# PCM2706_CODEC_MAIN.net
KiCad netlist of a schematic drawn in Altium Designer
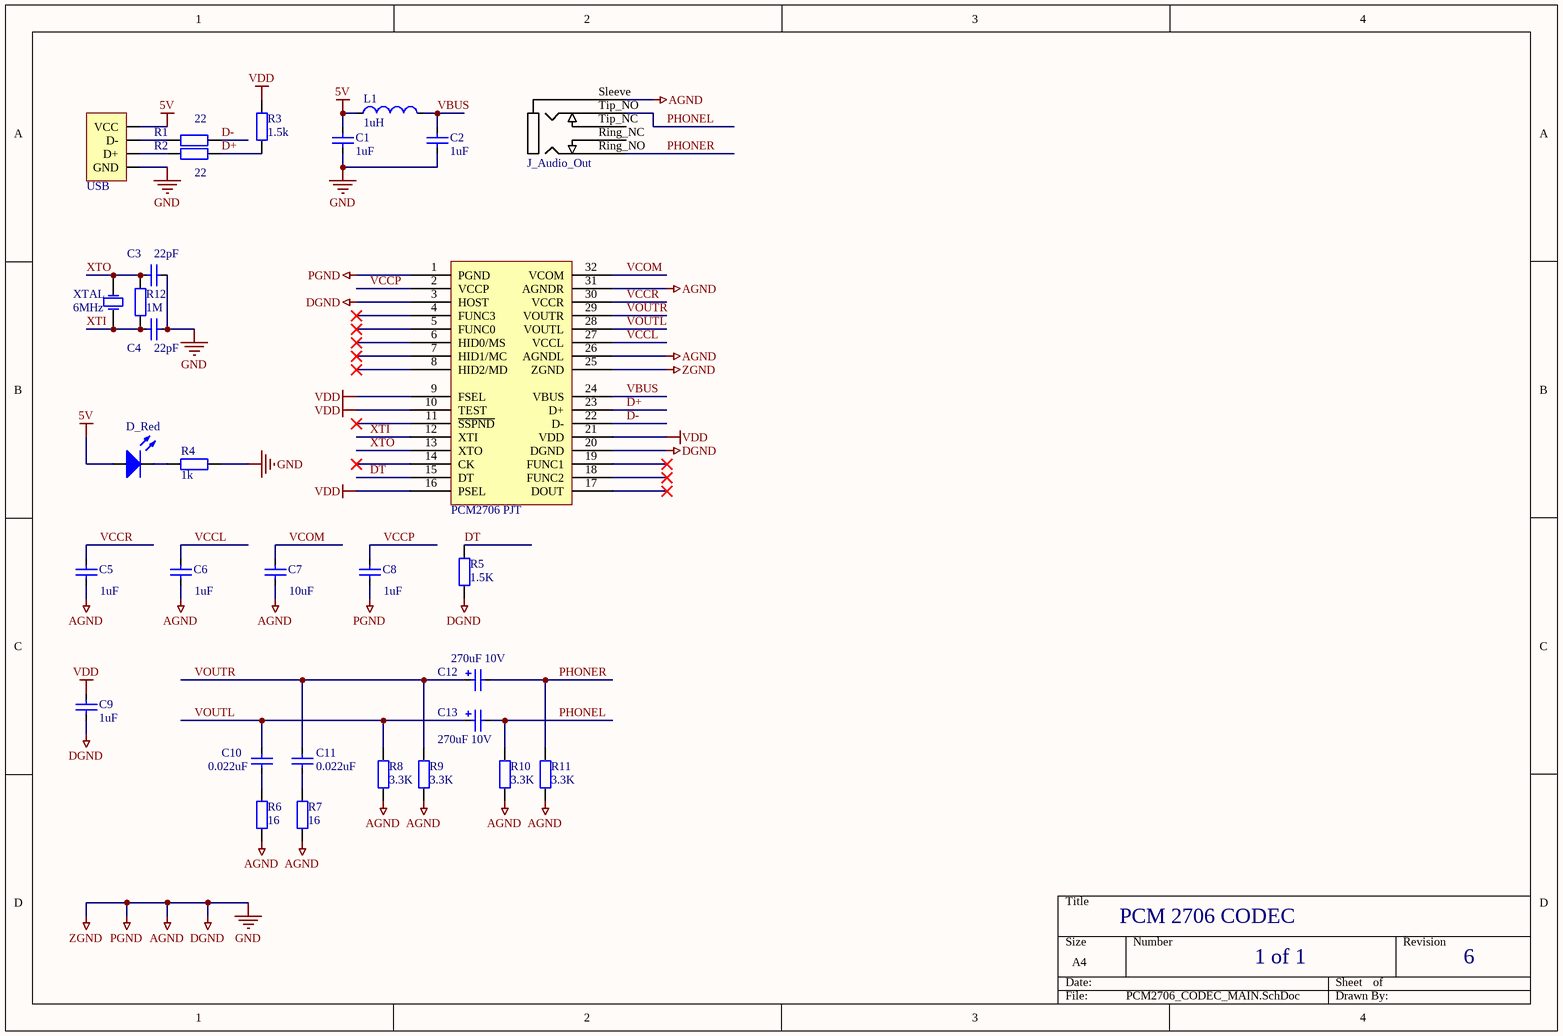
[diagram p0: PCM2706_CODEC_MAIN.SchDoc]

(export (version "E")
  (design (tool "Eeschema 10.0.6"))
  (components
    (comp (ref "C1")
      (value "1uF")
      (footprint "PCB_Passive:CAP_0603")
      (description "Capacitor")
      (fields (field (name "Comment") "Cap_0603"))
      (libsource (lib "SCH_Passive") (part "Cap_0603"))
    )
    (comp (ref "C2")
      (value "1uF")
      (footprint "PCB_Passive:CAP_0603")
      (description "Capacitor")
      (fields (field (name "Comment") "Cap_0603"))
      (libsource (lib "SCH_Passive") (part "Cap_0603"))
    )
    (comp (ref "C3")
      (value "22pF")
      (footprint "PCB_Passive:CAP_0603")
      (description "Capacitor")
      (fields (field (name "Comment") "Cap_0603"))
      (libsource (lib "SCH_Passive") (part "Cap_0603"))
    )
    (comp (ref "C4")
      (value "22pF")
      (footprint "PCB_Passive:CAP_0603")
      (description "Capacitor")
      (fields (field (name "Comment") "Cap_0603"))
      (libsource (lib "SCH_Passive") (part "Cap_0603"))
    )
    (comp (ref "C5")
      (value "1uF")
      (footprint "PCB_Passive:CAP_0603")
      (description "Cap_0603")
      (libsource (lib "SCH_Passive") (part "Cap_0603"))
    )
    (comp (ref "C6")
      (value "1uF")
      (footprint "PCB_Passive:CAP_0603")
      (description "Cap_0603")
      (libsource (lib "SCH_Passive") (part "Cap_0603"))
    )
    (comp (ref "C7")
      (value "10uF")
      (footprint "PCB_Passive:CAP_0603")
      (description "Cap_0603")
      (libsource (lib "SCH_Passive") (part "Cap_0603"))
    )
    (comp (ref "C8")
      (value "1uF")
      (footprint "PCB_Passive:CAP_0603")
      (description "Cap_0603")
      (libsource (lib "SCH_Passive") (part "Cap_0603"))
    )
    (comp (ref "C9")
      (value "1uF")
      (footprint "PCB_Passive:CAP_0603")
      (description "Cap_0603")
      (libsource (lib "SCH_Passive") (part "Cap_0603"))
    )
    (comp (ref "C10")
      (value "0.022uF")
      (footprint "PCB_Passive:CAP_0603")
      (description "Cap_0603")
      (libsource (lib "SCH_Passive") (part "Cap_0603"))
    )
    (comp (ref "C11")
      (value "0.022uF")
      (footprint "PCB_Passive:CAP_0603")
      (description "Cap_0603")
      (libsource (lib "SCH_Passive") (part "Cap_0603"))
    )
    (comp (ref "C12")
      (value "270uF 10V")
      (footprint "PCB_Passive:CAP_ELEC_F3.5_D8_H11.5")
      (description "Cap_ELEC_8*11.5*3.5")
      (fields (field (name "Comment") "270uF"))
      (libsource (lib "SCH_Passive") (part "Cap_ELEC_8*11.5*3.5"))
    )
    (comp (ref "C13")
      (value "270uF 10V")
      (footprint "PCB_Passive:CAP_ELEC_F3.5_D8_H11.5")
      (description "Cap_ELEC_8*11.5*3.5")
      (fields (field (name "Comment") "270uF"))
      (libsource (lib "SCH_Passive") (part "Cap_ELEC_8*11.5*3.5"))
    )
    (comp (ref "D_Red")
      (value "LED_0603_RED")
      (footprint "PCB_Active:LED_0603_RED")
      (description "LED")
      (libsource (lib "SCH_Active") (part "LED_0603_RED"))
    )
    (comp (ref "J_Audio_Out")
      (value "Generic 3.5 PhoneJack 5 Pin through-hole")
      (footprint "3.5 PhoneJack 5 Pin")
      (libsource (lib "SCH_Connector") (part "Generic 3.5 PhoneJack 5 Pin through-hole"))
    )
    (comp (ref "L1")
      (value "1uH")
      (footprint "PCB_Passive:IND_0603")
      (description "Inductor")
      (fields (field (name "Comment") "Ind_0603"))
      (libsource (lib "SCH_Passive") (part "Ind_0603"))
    )
    (comp (ref "PCM2706 PJT")
      (value "PCM2706 PJT")
      (footprint "TI-S-PQFP-N32")
      (description "PCM2706 USB CODEC")
      (libsource (lib "SCH_IC") (part "PCM2706 PJT"))
    )
    (comp (ref "R1")
      (value "22")
      (footprint "PCB_Passive:RES_0603")
      (description "Resistor")
      (fields (field (name "Comment") "Res_0603"))
      (libsource (lib "") (part "Res_0603_1"))
    )
    (comp (ref "R2")
      (value "22")
      (footprint "PCB_Passive:RES_0603")
      (description "Resistor")
      (fields (field (name "Comment") "Res_0603"))
      (libsource (lib "") (part "Res_0603_1"))
    )
    (comp (ref "R3")
      (value "1.5k")
      (footprint "PCB_Passive:RES_0603")
      (description "Resistor")
      (fields (field (name "Comment") "Res_0603"))
      (libsource (lib "SCH_Passive") (part "Res_0603"))
    )
    (comp (ref "R4")
      (value "1k")
      (footprint "PCB_Passive:RES_0603")
      (description "Res_0603")
      (libsource (lib "") (part "Res_0603_1"))
    )
    (comp (ref "R5")
      (value "1.5K")
      (footprint "PCB_Passive:RES_0603")
      (description "Resistor")
      (libsource (lib "SCH_Passive") (part "Res_0603"))
    )
    (comp (ref "R6")
      (value "16")
      (footprint "PCB_Passive:RES_0603")
      (description "Res_0603")
      (libsource (lib "SCH_Passive") (part "Res_0603"))
    )
    (comp (ref "R7")
      (value "16")
      (footprint "PCB_Passive:RES_0603")
      (description "Res_0603")
      (libsource (lib "SCH_Passive") (part "Res_0603"))
    )
    (comp (ref "R8")
      (value "3.3K")
      (footprint "PCB_Passive:RES_0603")
      (description "Res_0603")
      (libsource (lib "SCH_Passive") (part "Res_0603"))
    )
    (comp (ref "R9")
      (value "3.3K")
      (footprint "PCB_Passive:RES_0603")
      (description "Res_0603")
      (libsource (lib "SCH_Passive") (part "Res_0603"))
    )
    (comp (ref "R10")
      (value "3.3K")
      (footprint "PCB_Passive:RES_0603")
      (description "Res_0603")
      (libsource (lib "SCH_Passive") (part "Res_0603"))
    )
    (comp (ref "R11")
      (value "3.3K")
      (footprint "PCB_Passive:RES_0603")
      (description "Res_0603")
      (libsource (lib "SCH_Passive") (part "Res_0603"))
    )
    (comp (ref "R12")
      (value "1M")
      (footprint "PCB_Passive:RES_0603")
      (description "Resistor")
      (fields (field (name "Comment") "Res_0603"))
      (libsource (lib "SCH_Passive") (part "Res_0603"))
    )
    (comp (ref "USB") (value "USB") (footprint "PCB_USB:USB") (libsource (lib "SCH_USB") (part "USB")))
    (comp (ref "XTAL")
      (value "6MHz")
      (footprint "PCB_Oscillator:XTAL_5032")
      (description "Crystal Oscillator")
      (fields (field (name "Comment") "XTAL_5032") (field (name "PUBLISHER") "Altium Limited"))
      (libsource (lib "SCH_Oscillator") (part "XTAL_5032"))
    )
  )
  (nets
    (net (code "1") (name "/D+") (class "Default")
      (node (ref "PCM2706 PJT") (pin "23") (pinfunction "D+_23") (pintype "passive"))
      (node (ref "R2") (pin "2") (pinfunction "2_2") (pintype "passive"))
      (node (ref "R3") (pin "2") (pinfunction "2_2") (pintype "passive"))
    )
    (net (code "2") (name "/D-") (class "Default")
      (node (ref "PCM2706 PJT") (pin "22") (pinfunction "D-_22") (pintype "passive"))
      (node (ref "R1") (pin "2") (pinfunction "2_2") (pintype "passive"))
    )
    (net (code "3") (name "/DT") (class "Default")
      (node (ref "PCM2706 PJT") (pin "15") (pinfunction "DT_15") (pintype "passive"))
      (node (ref "R5") (pin "1") (pinfunction "1_1") (pintype "passive"))
    )
    (net (code "4") (name "/PHONEL") (class "Default")
      (node (ref "C13") (pin "2") (pinfunction "2_2") (pintype "passive"))
      (node (ref "J_Audio_Out") (pin "Tip_NO") (pinfunction "Tip_NO_Tip_NO") (pintype "passive"))
      (node (ref "R10") (pin "1") (pinfunction "1_1") (pintype "passive"))
    )
    (net (code "5") (name "/PHONER") (class "Default")
      (node (ref "C12") (pin "2") (pinfunction "2_2") (pintype "passive"))
      (node (ref "J_Audio_Out") (pin "Ring_NO") (pinfunction "Ring_NO_Ring_NO") (pintype "passive"))
      (node (ref "R11") (pin "1") (pinfunction "1_1") (pintype "passive"))
    )
    (net (code "6") (name "/VBUS") (class "Default")
      (node (ref "C2") (pin "2") (pinfunction "2_2") (pintype "passive"))
      (node (ref "L1") (pin "2") (pinfunction "2_2") (pintype "passive"))
      (node (ref "PCM2706 PJT") (pin "24") (pinfunction "VBUS_24") (pintype "passive"))
    )
    (net (code "7") (name "/VCCL") (class "Default")
      (node (ref "C6") (pin "2") (pinfunction "2_2") (pintype "passive"))
      (node (ref "PCM2706 PJT") (pin "27") (pinfunction "VCCL_27") (pintype "passive"))
    )
    (net (code "8") (name "/VCCP") (class "Default")
      (node (ref "C8") (pin "2") (pinfunction "2_2") (pintype "passive"))
      (node (ref "PCM2706 PJT") (pin "2") (pinfunction "VCCP_2") (pintype "passive"))
    )
    (net (code "9") (name "/VCCR") (class "Default")
      (node (ref "C5") (pin "2") (pinfunction "2_2") (pintype "passive"))
      (node (ref "PCM2706 PJT") (pin "30") (pinfunction "VCCR_30") (pintype "passive"))
    )
    (net (code "10") (name "/VCOM") (class "Default")
      (node (ref "C7") (pin "2") (pinfunction "2_2") (pintype "passive"))
      (node (ref "PCM2706 PJT") (pin "32") (pinfunction "VCOM_32") (pintype "passive"))
    )
    (net (code "11") (name "/VOUTL") (class "Default")
      (node (ref "C10") (pin "2") (pinfunction "2_2") (pintype "passive"))
      (node (ref "C13") (pin "1") (pinfunction "1_1") (pintype "passive"))
      (node (ref "PCM2706 PJT") (pin "28") (pinfunction "VOUTL_28") (pintype "passive"))
      (node (ref "R8") (pin "1") (pinfunction "1_1") (pintype "passive"))
    )
    (net (code "12") (name "/VOUTR") (class "Default")
      (node (ref "C11") (pin "2") (pinfunction "2_2") (pintype "passive"))
      (node (ref "C12") (pin "1") (pinfunction "1_1") (pintype "passive"))
      (node (ref "PCM2706 PJT") (pin "29") (pinfunction "VOUTR_29") (pintype "passive"))
      (node (ref "R9") (pin "1") (pinfunction "1_1") (pintype "passive"))
    )
    (net (code "13") (name "/XTI") (class "Default")
      (node (ref "C4") (pin "2") (pinfunction "2_2") (pintype "passive"))
      (node (ref "PCM2706 PJT") (pin "12") (pinfunction "XTI_12") (pintype "passive"))
      (node (ref "R12") (pin "2") (pinfunction "2_2") (pintype "passive"))
      (node (ref "XTAL") (pin "1") (pinfunction "OSC1_1") (pintype "passive"))
    )
    (net (code "14") (name "/XTO") (class "Default")
      (node (ref "C3") (pin "2") (pinfunction "2_2") (pintype "passive"))
      (node (ref "PCM2706 PJT") (pin "13") (pinfunction "XTO_13") (pintype "passive"))
      (node (ref "R12") (pin "1") (pinfunction "1_1") (pintype "passive"))
      (node (ref "XTAL") (pin "2") (pinfunction "OSC2_2") (pintype "passive"))
    )
    (net (code "15") (name "5V") (class "Default")
      (node (ref "C1") (pin "2") (pinfunction "2_2") (pintype "passive"))
      (node (ref "D_Red") (pin "1") (pinfunction "A_1") (pintype "passive"))
      (node (ref "L1") (pin "1") (pinfunction "1_1") (pintype "passive"))
      (node (ref "USB") (pin "1") (pinfunction "VCC_1") (pintype "passive"))
    )
    (net (code "16") (name "AGND") (class "Default")
      (node (ref "C1") (pin "1") (pinfunction "1_1") (pintype "passive"))
      (node (ref "C2") (pin "1") (pinfunction "1_1") (pintype "passive"))
      (node (ref "C3") (pin "1") (pinfunction "1_1") (pintype "passive"))
      (node (ref "C4") (pin "1") (pinfunction "1_1") (pintype "passive"))
      (node (ref "C5") (pin "1") (pinfunction "1_1") (pintype "passive"))
      (node (ref "C6") (pin "1") (pinfunction "1_1") (pintype "passive"))
      (node (ref "C7") (pin "1") (pinfunction "1_1") (pintype "passive"))
      (node (ref "C8") (pin "1") (pinfunction "1_1") (pintype "passive"))
      (node (ref "C9") (pin "1") (pinfunction "1_1") (pintype "passive"))
      (node (ref "J_Audio_Out") (pin "Sleeve") (pinfunction "Sleeve_Sleeve") (pintype "passive"))
      (node (ref "PCM2706 PJT") (pin "1") (pinfunction "PGND_1") (pintype "passive"))
      (node (ref "PCM2706 PJT") (pin "20") (pinfunction "DGND_20") (pintype "passive"))
      (node (ref "PCM2706 PJT") (pin "25") (pinfunction "ZGND_25") (pintype "passive"))
      (node (ref "PCM2706 PJT") (pin "26") (pinfunction "AGNDL_26") (pintype "passive"))
      (node (ref "PCM2706 PJT") (pin "3") (pinfunction "HOST_3") (pintype "passive"))
      (node (ref "PCM2706 PJT") (pin "31") (pinfunction "AGNDR_31") (pintype "passive"))
      (node (ref "R10") (pin "2") (pinfunction "2_2") (pintype "passive"))
      (node (ref "R11") (pin "2") (pinfunction "2_2") (pintype "passive"))
      (node (ref "R4") (pin "2") (pinfunction "2_2") (pintype "passive"))
      (node (ref "R5") (pin "2") (pinfunction "2_2") (pintype "passive"))
      (node (ref "R6") (pin "2") (pinfunction "2_2") (pintype "passive"))
      (node (ref "R7") (pin "2") (pinfunction "2_2") (pintype "passive"))
      (node (ref "R8") (pin "2") (pinfunction "2_2") (pintype "passive"))
      (node (ref "R9") (pin "2") (pinfunction "2_2") (pintype "passive"))
      (node (ref "USB") (pin "4") (pinfunction "GND_4") (pintype "passive"))
    )
    (net (code "17") (name "Net-(C10-Pad1)") (class "Default")
      (node (ref "C10") (pin "1") (pinfunction "1_1") (pintype "passive"))
      (node (ref "R6") (pin "1") (pinfunction "1_1") (pintype "passive"))
    )
    (net (code "18") (name "Net-(C11-Pad1)") (class "Default")
      (node (ref "C11") (pin "1") (pinfunction "1_1") (pintype "passive"))
      (node (ref "R7") (pin "1") (pinfunction "1_1") (pintype "passive"))
    )
    (net (code "19") (name "Net-(D_Red-K)") (class "Default")
      (node (ref "D_Red") (pin "2") (pinfunction "K_2") (pintype "passive"))
      (node (ref "R4") (pin "1") (pinfunction "1_1") (pintype "passive"))
    )
    (net (code "20") (name "Net-(USB-D+)") (class "Default")
      (node (ref "R2") (pin "1") (pinfunction "1_1") (pintype "passive"))
      (node (ref "USB") (pin "3") (pinfunction "D+_3") (pintype "passive"))
    )
    (net (code "21") (name "Net-(USB-D-)") (class "Default")
      (node (ref "R1") (pin "1") (pinfunction "1_1") (pintype "passive"))
      (node (ref "USB") (pin "2") (pinfunction "D-_2") (pintype "passive"))
    )
    (net (code "22") (name "VDD") (class "Default")
      (node (ref "C9") (pin "2") (pinfunction "2_2") (pintype "passive"))
      (node (ref "PCM2706 PJT") (pin "10") (pinfunction "TEST_10") (pintype "passive"))
      (node (ref "PCM2706 PJT") (pin "16") (pinfunction "PSEL_16") (pintype "passive"))
      (node (ref "PCM2706 PJT") (pin "21") (pinfunction "VDD_21") (pintype "passive"))
      (node (ref "PCM2706 PJT") (pin "9") (pinfunction "FSEL_9") (pintype "passive"))
      (node (ref "R3") (pin "1") (pinfunction "1_1") (pintype "passive"))
    )
    (net (code "23") (name "unconnected-(J_Audio_Out-PadRing_NC)") (class "Default")
      (node (ref "J_Audio_Out") (pin "Ring_NC") (pinfunction "Ring_NC_Ring_NC") (pintype "passive"))
    )
    (net (code "24") (name "unconnected-(J_Audio_Out-PadTip_NC)") (class "Default")
      (node (ref "J_Audio_Out") (pin "Tip_NC") (pinfunction "Tip_NC_Tip_NC") (pintype "passive"))
    )
    (net (code "25") (name "unconnected-(PCM2706 PJT-CK-Pad14)") (class "Default")
      (node (ref "PCM2706 PJT") (pin "14") (pinfunction "CK_14") (pintype "passive+no_connect"))
    )
    (net (code "26") (name "unconnected-(PCM2706 PJT-DOUT-Pad17)") (class "Default")
      (node (ref "PCM2706 PJT") (pin "17") (pinfunction "DOUT_17") (pintype "passive+no_connect"))
    )
    (net (code "27") (name "unconnected-(PCM2706 PJT-FUNC0-Pad5)") (class "Default")
      (node (ref "PCM2706 PJT") (pin "5") (pinfunction "FUNC0_5") (pintype "passive+no_connect"))
    )
    (net (code "28") (name "unconnected-(PCM2706 PJT-FUNC1-Pad19)") (class "Default")
      (node (ref "PCM2706 PJT") (pin "19") (pinfunction "FUNC1_19") (pintype "passive+no_connect"))
    )
    (net (code "29") (name "unconnected-(PCM2706 PJT-FUNC2-Pad18)") (class "Default")
      (node (ref "PCM2706 PJT") (pin "18") (pinfunction "FUNC2_18") (pintype "passive+no_connect"))
    )
    (net (code "30") (name "unconnected-(PCM2706 PJT-FUNC3-Pad4)") (class "Default")
      (node (ref "PCM2706 PJT") (pin "4") (pinfunction "FUNC3_4") (pintype "passive+no_connect"))
    )
    (net (code "31") (name "unconnected-(PCM2706 PJT-HID0{slash}MS-Pad6)") (class "Default")
      (node (ref "PCM2706 PJT") (pin "6") (pinfunction "HID0/MS_6") (pintype "passive+no_connect"))
    )
    (net (code "32") (name "unconnected-(PCM2706 PJT-HID1{slash}MC-Pad7)") (class "Default")
      (node (ref "PCM2706 PJT") (pin "7") (pinfunction "HID1/MC_7") (pintype "passive+no_connect"))
    )
    (net (code "33") (name "unconnected-(PCM2706 PJT-HID2{slash}MD-Pad8)") (class "Default")
      (node (ref "PCM2706 PJT") (pin "8") (pinfunction "HID2/MD_8") (pintype "passive+no_connect"))
    )
    (net (code "34") (name "unconnected-(PCM2706 PJT-~{SSPND}-Pad11)") (class "Default")
      (node (ref "PCM2706 PJT") (pin "11") (pinfunction "~{SSPND}_11") (pintype "passive+no_connect"))
    )
  )
)
